# firefly099.net
KiCad netlist of a schematic drawn in EAGLE
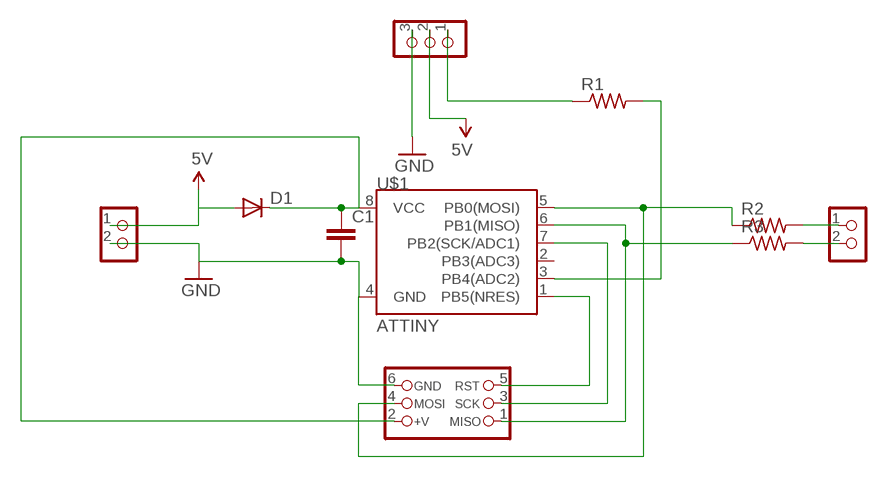
[diagram p0: schematic, sheet 1]

(export (version "E")
  (design (tool "Eeschema 10.0.6"))
  (components
    (comp (ref "-,+")
      (value "CON_TERMINAL_BLOCK_02-5MM")
      (footprint "eagle-import:TERMINAL_BLOCK_2P_5")
      (libsource (lib "eagle-import") (part "CON_TERMINAL_BLOCK_02-5MM"))
    )
    (comp (ref "C1")
      (value "CAPPTH")
      (footprint "eagle-import:CAP-PTH-SMALL")
      (libsource (lib "eagle-import") (part "CAPPTH"))
    )
    (comp (ref "D1")
      (value "1N4004")
      (footprint "eagle-import:DO41-10")
      (libsource (lib "eagle-import") (part "1N4004"))
    )
    (comp (ref "IO")
      (value "CON_TERMINAL_BLOCK_02-5MM")
      (footprint "eagle-import:TERMINAL_BLOCK_2P_5")
      (libsource (lib "eagle-import") (part "CON_TERMINAL_BLOCK_02-5MM"))
    )
    (comp (ref "J3")
      (value "CON_HEADER_PRG_AVR_ICSP-PTH")
      (footprint "eagle-import:HEADER_PRG_2X03")
      (libsource (lib "eagle-import") (part "CON_HEADER_PRG_AVR_ICSP-PTH"))
    )
    (comp (ref "LED")
      (value "CON_TERMINAL_BLOCK_03-5MM")
      (footprint "eagle-import:TERMINAL_BLOCK_3P_5")
      (libsource (lib "eagle-import") (part "CON_TERMINAL_BLOCK_03-5MM"))
    )
    (comp (ref "R1")
      (value "R-US_0207/2V")
      (footprint "eagle-import:0207_2V")
      (libsource (lib "eagle-import") (part "R-US_0207/2V"))
    )
    (comp (ref "R2")
      (value "R-US_0207/2V")
      (footprint "eagle-import:0207_2V")
      (libsource (lib "eagle-import") (part "R-US_0207/2V"))
    )
    (comp (ref "R3")
      (value "R-US_0207/2V")
      (footprint "eagle-import:0207_2V")
      (libsource (lib "eagle-import") (part "R-US_0207/2V"))
    )
    (comp (ref "U$1")
      (value "ATTINY")
      (footprint "eagle-import:DIP08")
      (libsource (lib "eagle-import") (part "ATTINY45DIP8"))
    )
  )
  (nets
    (net (code "1") (name "5V") (class "Default")
      (node (ref "-,+") (pin "1") (pinfunction "1_1") (pintype "passive"))
      (node (ref "D1") (pin "A") (pinfunction "A_A") (pintype "passive"))
      (node (ref "LED") (pin "2") (pinfunction "2_2") (pintype "bidirectional"))
    )
    (net (code "2") (name "GND") (class "Default")
      (node (ref "-,+") (pin "2") (pinfunction "2_2") (pintype "passive"))
      (node (ref "C1") (pin "2") (pinfunction "2_2") (pintype "passive"))
      (node (ref "J3") (pin "6") (pinfunction "GND_6") (pintype "passive"))
      (node (ref "LED") (pin "3") (pinfunction "3_3") (pintype "bidirectional"))
      (node (ref "U$1") (pin "4") (pinfunction "GND_4") (pintype "bidirectional"))
    )
    (net (code "3") (name "Net-(IO-Pad1)") (class "Default")
      (node (ref "IO") (pin "1") (pinfunction "1_1") (pintype "passive"))
      (node (ref "R2") (pin "2") (pinfunction "2_2") (pintype "passive"))
    )
    (net (code "4") (name "Net-(IO-Pad2)") (class "Default")
      (node (ref "IO") (pin "2") (pinfunction "2_2") (pintype "passive"))
      (node (ref "R3") (pin "2") (pinfunction "2_2") (pintype "passive"))
    )
    (net (code "5") (name "Net-(J3-+V)") (class "Default")
      (node (ref "C1") (pin "1") (pinfunction "1_1") (pintype "passive"))
      (node (ref "D1") (pin "C") (pinfunction "C_C") (pintype "passive"))
      (node (ref "J3") (pin "2") (pinfunction "+V_2") (pintype "passive"))
      (node (ref "U$1") (pin "8") (pinfunction "VCC_8") (pintype "bidirectional"))
    )
    (net (code "6") (name "Net-(J3-MISO)") (class "Default")
      (node (ref "J3") (pin "1") (pinfunction "MISO_1") (pintype "passive"))
      (node (ref "R3") (pin "1") (pinfunction "1_1") (pintype "passive"))
      (node (ref "U$1") (pin "6") (pinfunction "PB1(MISO)_6") (pintype "bidirectional"))
    )
    (net (code "7") (name "Net-(J3-MOSI)") (class "Default")
      (node (ref "J3") (pin "4") (pinfunction "MOSI_4") (pintype "passive"))
      (node (ref "R2") (pin "1") (pinfunction "1_1") (pintype "passive"))
      (node (ref "U$1") (pin "5") (pinfunction "PB0(MOSI)_5") (pintype "bidirectional"))
    )
    (net (code "8") (name "Net-(J3-RST)") (class "Default")
      (node (ref "J3") (pin "5") (pinfunction "RST_5") (pintype "passive"))
      (node (ref "U$1") (pin "1") (pinfunction "PB5(NRES)_1") (pintype "bidirectional"))
    )
    (net (code "9") (name "Net-(J3-SCK)") (class "Default")
      (node (ref "J3") (pin "3") (pinfunction "SCK_3") (pintype "passive"))
      (node (ref "U$1") (pin "7") (pinfunction "PB2(SCK/ADC1)_7") (pintype "bidirectional"))
    )
    (net (code "10") (name "Net-(LED-Pad1)") (class "Default")
      (node (ref "LED") (pin "1") (pinfunction "1_1") (pintype "bidirectional"))
      (node (ref "R1") (pin "1") (pinfunction "1_1") (pintype "passive"))
    )
    (net (code "11") (name "Net-(U$1-PB4(ADC2))") (class "Default")
      (node (ref "R1") (pin "2") (pinfunction "2_2") (pintype "passive"))
      (node (ref "U$1") (pin "3") (pinfunction "PB4(ADC2)_3") (pintype "bidirectional"))
    )
    (net (code "12") (name "unconnected-(U$1-PB3(ADC3)-Pad2)") (class "Default")
      (node (ref "U$1") (pin "2") (pinfunction "PB3(ADC3)_2") (pintype "bidirectional"))
    )
  )
)
